# colorimeter.net
KiCad netlist of a schematic drawn in EAGLE
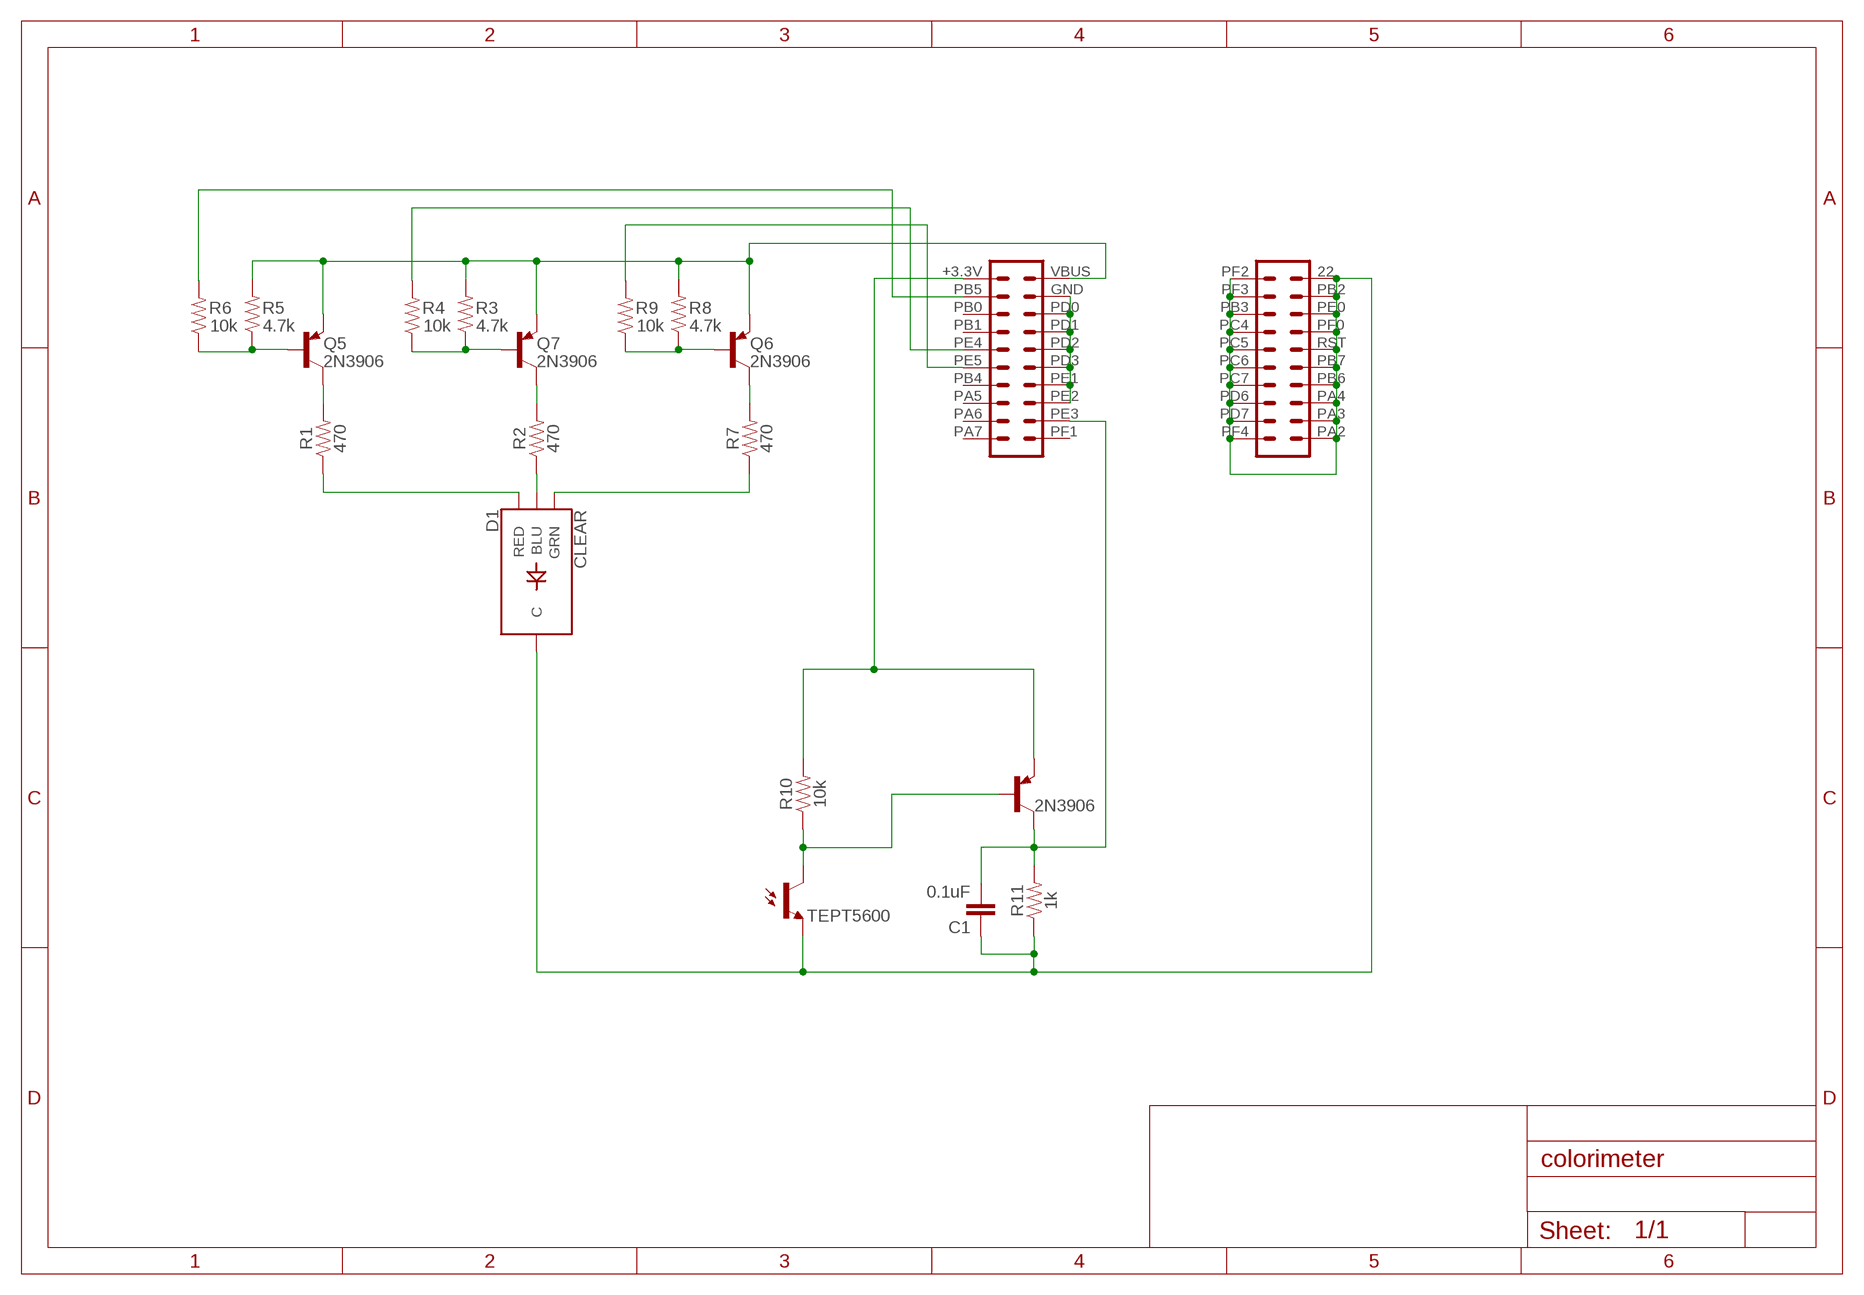
[diagram p0: schematic, sheet 1]

(export (version "E")
  (design (tool "Eeschema 10.0.6"))
  (components
    (comp (ref "C1")
      (value "0.1uF")
      (footprint "eagle-import:CAP-PTH-SMALL-KIT")
      (libsource (lib "eagle-import") (part "0.1UF-KIT-EZ-50V-20%"))
    )
    (comp (ref "D1")
      (value "CLEAR")
      (footprint "eagle-import:LED-RGB-THRU")
      (libsource (lib "eagle-import") (part "LED-RGB-CCCLEAR"))
    )
    (comp (ref "Q1")
      (value "TEPT5600")
      (footprint "eagle-import:PT17-21C-L41-TR8")
      (libsource (lib "eagle-import") (part "PHOTOTRANSISTORPT17-21C-L41-TR8"))
    )
    (comp (ref "Q5")
      (value "2N3906")
      (footprint "eagle-import:TO92-EBC-OVAL")
      (libsource (lib "eagle-import") (part "2N2907"))
    )
    (comp (ref "Q6")
      (value "2N3906")
      (footprint "eagle-import:TO92-EBC-OVAL")
      (libsource (lib "eagle-import") (part "2N2907"))
    )
    (comp (ref "Q7")
      (value "2N3906")
      (footprint "eagle-import:TO92-EBC-OVAL")
      (libsource (lib "eagle-import") (part "2N2907"))
    )
    (comp (ref "R1")
      (value "470")
      (footprint "eagle-import:AXIAL-0.3")
      (libsource (lib "eagle-import") (part "1KOHM-HORIZ-1/4W-5%"))
    )
    (comp (ref "R2")
      (value "470")
      (footprint "eagle-import:AXIAL-0.3")
      (libsource (lib "eagle-import") (part "1KOHM-HORIZ-1/4W-5%"))
    )
    (comp (ref "R3")
      (value "4.7k")
      (footprint "eagle-import:AXIAL-0.3")
      (libsource (lib "eagle-import") (part "1KOHM-HORIZ-1/4W-5%"))
    )
    (comp (ref "R4")
      (value "10k")
      (footprint "eagle-import:AXIAL-0.3")
      (libsource (lib "eagle-import") (part "1KOHM-HORIZ-1/4W-5%"))
    )
    (comp (ref "R5")
      (value "4.7k")
      (footprint "eagle-import:AXIAL-0.3")
      (libsource (lib "eagle-import") (part "1KOHM-HORIZ-1/4W-5%"))
    )
    (comp (ref "R6")
      (value "10k")
      (footprint "eagle-import:AXIAL-0.3")
      (libsource (lib "eagle-import") (part "1KOHM-HORIZ-1/4W-5%"))
    )
    (comp (ref "R7")
      (value "470")
      (footprint "eagle-import:AXIAL-0.3")
      (libsource (lib "eagle-import") (part "1KOHM-HORIZ-1/4W-5%"))
    )
    (comp (ref "R8")
      (value "4.7k")
      (footprint "eagle-import:AXIAL-0.3")
      (libsource (lib "eagle-import") (part "1KOHM-HORIZ-1/4W-5%"))
    )
    (comp (ref "R9")
      (value "10k")
      (footprint "eagle-import:AXIAL-0.3")
      (libsource (lib "eagle-import") (part "1KOHM-HORIZ-1/4W-5%"))
    )
    (comp (ref "R10")
      (value "10k")
      (footprint "eagle-import:AXIAL-0.3")
      (libsource (lib "eagle-import") (part "10KOHM-HORIZ-1/4W-1%"))
    )
    (comp (ref "R11")
      (value "1k")
      (footprint "eagle-import:AXIAL-0.3")
      (libsource (lib "eagle-import") (part "10KOHM-HORIZ-1/4W-1%"))
    )
    (comp (ref "T2")
      (value "2N3906")
      (footprint "eagle-import:TO92-EBC")
      (libsource (lib "eagle-import") (part "-PNP-TO92-EBC2N3906"))
    )
    (comp (ref "U$1")
      (value "LAUNCHPAD_PINS")
      (footprint "eagle-import:LAUNCHPAD_PINS")
      (libsource (lib "eagle-import") (part "LAUNCHPAD_PINS"))
    )
  )
  (nets
    (net (code "1") (name "Net-(D1-BLU)") (class "Default")
      (node (ref "D1") (pin "4") (pinfunction "BLU_4") (pintype "bidirectional"))
      (node (ref "R2") (pin "P$1") (pinfunction "1_P$1") (pintype "passive"))
    )
    (net (code "2") (name "Net-(D1-C)") (class "Default")
      (node (ref "C1") (pin "1") (pinfunction "1_1") (pintype "passive"))
      (node (ref "D1") (pin "2") (pinfunction "C_2") (pintype "bidirectional"))
      (node (ref "Q1") (pin "E") (pinfunction "E_E") (pintype "passive"))
      (node (ref "R11") (pin "P$1") (pinfunction "1_P$1") (pintype "passive"))
      (node (ref "U$1") (pin "22") (pinfunction "2_22") (pintype "passive"))
      (node (ref "U$1") (pin "PA2") (pinfunction "20_PA2") (pintype "passive"))
      (node (ref "U$1") (pin "PA3") (pinfunction "18_PA3") (pintype "passive"))
      (node (ref "U$1") (pin "PA4") (pinfunction "16_PA4") (pintype "passive"))
      (node (ref "U$1") (pin "PB2") (pinfunction "4_PB2") (pintype "passive"))
      (node (ref "U$1") (pin "PB3") (pinfunction "5_PB3") (pintype "passive"))
      (node (ref "U$1") (pin "PB6") (pinfunction "14_PB6") (pintype "passive"))
      (node (ref "U$1") (pin "PB7") (pinfunction "12_PB7") (pintype "passive"))
      (node (ref "U$1") (pin "PC4") (pinfunction "7_PC4") (pintype "passive"))
      (node (ref "U$1") (pin "PC5") (pinfunction "9_PC5") (pintype "passive"))
      (node (ref "U$1") (pin "PC6") (pinfunction "11_PC6") (pintype "passive"))
      (node (ref "U$1") (pin "PC7") (pinfunction "13_PC7") (pintype "passive"))
      (node (ref "U$1") (pin "PD6") (pinfunction "15_PD6") (pintype "passive"))
      (node (ref "U$1") (pin "PD7") (pinfunction "17_PD7") (pintype "passive"))
      (node (ref "U$1") (pin "PE0") (pinfunction "6_PE0") (pintype "passive"))
      (node (ref "U$1") (pin "PF0") (pinfunction "8_PF0") (pintype "passive"))
      (node (ref "U$1") (pin "PF2") (pinfunction "1_PF2") (pintype "passive"))
      (node (ref "U$1") (pin "PF3") (pinfunction "3_PF3") (pintype "passive"))
      (node (ref "U$1") (pin "PF4") (pinfunction "19_PF4") (pintype "passive"))
      (node (ref "U$1") (pin "RST") (pinfunction "10_RST") (pintype "passive"))
    )
    (net (code "3") (name "Net-(D1-GRN)") (class "Default")
      (node (ref "D1") (pin "3") (pinfunction "GRN_3") (pintype "bidirectional"))
      (node (ref "R7") (pin "P$1") (pinfunction "1_P$1") (pintype "passive"))
    )
    (net (code "4") (name "Net-(D1-RED)") (class "Default")
      (node (ref "D1") (pin "1") (pinfunction "RED_1") (pintype "bidirectional"))
      (node (ref "R1") (pin "P$1") (pinfunction "1_P$1") (pintype "passive"))
    )
    (net (code "5") (name "Net-(R1-2)") (class "Default")
      (node (ref "Q5") (pin "C") (pinfunction "C_C") (pintype "passive"))
      (node (ref "R1") (pin "P$2") (pinfunction "2_P$2") (pintype "passive"))
    )
    (net (code "6") (name "Net-(R2-2)") (class "Default")
      (node (ref "Q7") (pin "C") (pinfunction "C_C") (pintype "passive"))
      (node (ref "R2") (pin "P$2") (pinfunction "2_P$2") (pintype "passive"))
    )
    (net (code "7") (name "Net-(R3-1)") (class "Default")
      (node (ref "Q7") (pin "B") (pinfunction "B_B") (pintype "passive"))
      (node (ref "R3") (pin "P$1") (pinfunction "1_P$1") (pintype "passive"))
      (node (ref "R4") (pin "P$1") (pinfunction "1_P$1") (pintype "passive"))
    )
    (net (code "8") (name "Net-(R3-2)") (class "Default")
      (node (ref "Q5") (pin "E") (pinfunction "E_E") (pintype "passive"))
      (node (ref "Q6") (pin "E") (pinfunction "E_E") (pintype "passive"))
      (node (ref "Q7") (pin "E") (pinfunction "E_E") (pintype "passive"))
      (node (ref "R3") (pin "P$2") (pinfunction "2_P$2") (pintype "passive"))
      (node (ref "R5") (pin "P$2") (pinfunction "2_P$2") (pintype "passive"))
      (node (ref "R8") (pin "P$2") (pinfunction "2_P$2") (pintype "passive"))
      (node (ref "U$1") (pin "VBUS") (pinfunction "22_VBUS") (pintype "power_in"))
    )
    (net (code "9") (name "Net-(R4-2)") (class "Default")
      (node (ref "R4") (pin "P$2") (pinfunction "2_P$2") (pintype "passive"))
      (node (ref "U$1") (pin "PE4") (pinfunction "29_PE4") (pintype "passive"))
    )
    (net (code "10") (name "Net-(R5-1)") (class "Default")
      (node (ref "Q5") (pin "B") (pinfunction "B_B") (pintype "passive"))
      (node (ref "R5") (pin "P$1") (pinfunction "1_P$1") (pintype "passive"))
      (node (ref "R6") (pin "P$1") (pinfunction "1_P$1") (pintype "passive"))
    )
    (net (code "11") (name "Net-(R6-2)") (class "Default")
      (node (ref "R6") (pin "P$2") (pinfunction "2_P$2") (pintype "passive"))
      (node (ref "U$1") (pin "PB5") (pinfunction "23_PB5") (pintype "passive"))
    )
    (net (code "12") (name "Net-(R7-2)") (class "Default")
      (node (ref "Q6") (pin "C") (pinfunction "C_C") (pintype "passive"))
      (node (ref "R7") (pin "P$2") (pinfunction "2_P$2") (pintype "passive"))
    )
    (net (code "13") (name "Net-(R8-1)") (class "Default")
      (node (ref "Q6") (pin "B") (pinfunction "B_B") (pintype "passive"))
      (node (ref "R8") (pin "P$1") (pinfunction "1_P$1") (pintype "passive"))
      (node (ref "R9") (pin "P$1") (pinfunction "1_P$1") (pintype "passive"))
    )
    (net (code "14") (name "Net-(R9-2)") (class "Default")
      (node (ref "R9") (pin "P$2") (pinfunction "2_P$2") (pintype "passive"))
      (node (ref "U$1") (pin "PE5") (pinfunction "31_PE5") (pintype "passive"))
    )
    (net (code "15") (name "Net-(R10-1)") (class "Default")
      (node (ref "Q1") (pin "C") (pinfunction "C_C") (pintype "passive"))
      (node (ref "R10") (pin "P$1") (pinfunction "1_P$1") (pintype "passive"))
      (node (ref "T2") (pin "B") (pinfunction "B_B") (pintype "passive"))
    )
    (net (code "16") (name "Net-(R10-2)") (class "Default")
      (node (ref "R10") (pin "P$2") (pinfunction "2_P$2") (pintype "passive"))
      (node (ref "T2") (pin "E") (pinfunction "E_E") (pintype "passive"))
      (node (ref "U$1") (pin "+3.3V") (pinfunction "21_+3.3V") (pintype "power_in"))
    )
    (net (code "17") (name "Net-(R11-2)") (class "Default")
      (node (ref "C1") (pin "2") (pinfunction "2_2") (pintype "passive"))
      (node (ref "R11") (pin "P$2") (pinfunction "2_P$2") (pintype "passive"))
      (node (ref "T2") (pin "C") (pinfunction "C_C") (pintype "passive"))
      (node (ref "U$1") (pin "PE3") (pinfunction "38_PE3") (pintype "passive"))
    )
    (net (code "18") (name "Net-(U$1-24)") (class "Default")
      (node (ref "U$1") (pin "GND") (pinfunction "24_GND") (pintype "passive"))
      (node (ref "U$1") (pin "PD0") (pinfunction "26_PD0") (pintype "passive"))
      (node (ref "U$1") (pin "PD1") (pinfunction "28_PD1") (pintype "passive"))
      (node (ref "U$1") (pin "PD2") (pinfunction "30_PD2") (pintype "passive"))
      (node (ref "U$1") (pin "PD3") (pinfunction "32_PD3") (pintype "passive"))
      (node (ref "U$1") (pin "PE1") (pinfunction "34_PE1") (pintype "passive"))
      (node (ref "U$1") (pin "PE2") (pinfunction "36_PE2") (pintype "passive"))
    )
    (net (code "19") (name "unconnected-(U$1-25-PadPB0)") (class "Default")
      (node (ref "U$1") (pin "PB0") (pinfunction "25_PB0") (pintype "passive"))
    )
    (net (code "20") (name "unconnected-(U$1-27-PadPB1)") (class "Default")
      (node (ref "U$1") (pin "PB1") (pinfunction "27_PB1") (pintype "passive"))
    )
    (net (code "21") (name "unconnected-(U$1-33-PadPB4)") (class "Default")
      (node (ref "U$1") (pin "PB4") (pinfunction "33_PB4") (pintype "passive"))
    )
    (net (code "22") (name "unconnected-(U$1-35-PadPA5)") (class "Default")
      (node (ref "U$1") (pin "PA5") (pinfunction "35_PA5") (pintype "passive"))
    )
    (net (code "23") (name "unconnected-(U$1-37-PadPA6)") (class "Default")
      (node (ref "U$1") (pin "PA6") (pinfunction "37_PA6") (pintype "passive"))
    )
    (net (code "24") (name "unconnected-(U$1-39-PadPA7)") (class "Default")
      (node (ref "U$1") (pin "PA7") (pinfunction "39_PA7") (pintype "passive"))
    )
    (net (code "25") (name "unconnected-(U$1-40-PadPF1)") (class "Default")
      (node (ref "U$1") (pin "PF1") (pinfunction "40_PF1") (pintype "passive"))
    )
  )
)
